# FTDI.net
KiCad netlist of a schematic drawn in Altium Designer
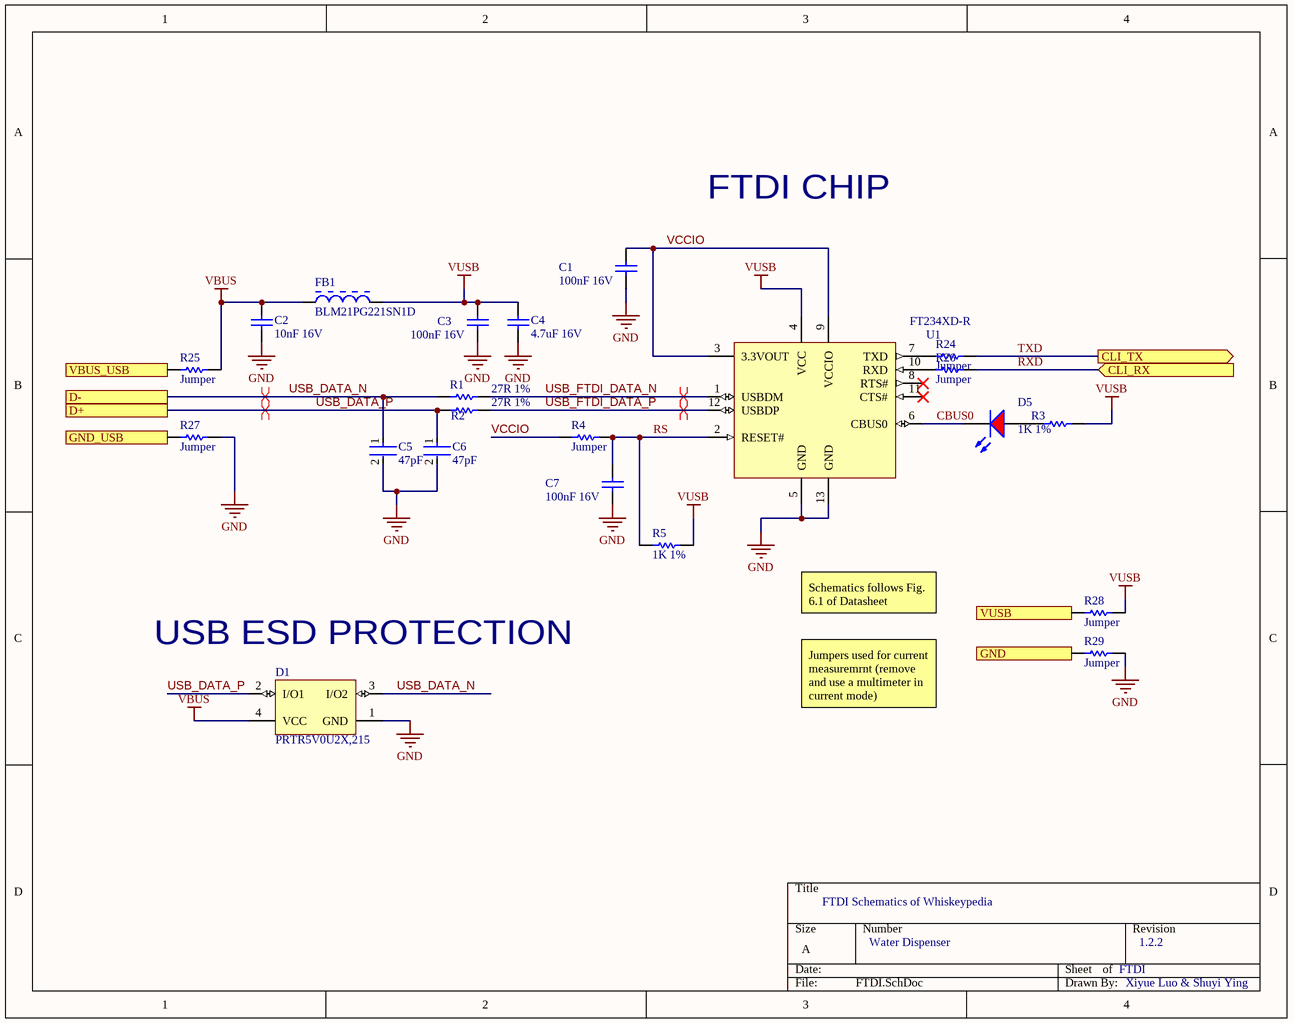
[diagram p0: FTDI.SchDoc]

(export (version "E")
  (design (tool "Eeschema 10.0.6"))
  (components
    (comp (ref "C1")
      (value "100nF 16V")
      (footprint "CAPC0603(1608)100_N")
      (description "CAP 100nF 16V ±10% 0603 (1608 Metric) Thickness 1mm SMD")
      (fields (field (name "TOLERANCE") "Â±10%"))
      (libsource (lib "Altium Content Vault") (part "CAP"))
    )
    (comp (ref "C2")
      (value "10nF 16V")
      (footprint "CAPC0603(1608)100_N")
      (description "CAP 10nF 16V ±10% 0603 (1608 Metric) Thickness 1mm SMD")
      (fields (field (name "TOLERANCE") "Â±10%"))
      (libsource (lib "Altium Content Vault") (part "CAP"))
    )
    (comp (ref "C3")
      (value "100nF 16V")
      (footprint "CAPC0603(1608)100_N")
      (description "CAP 100nF 16V ±10% 0603 (1608 Metric) Thickness 1mm SMD")
      (fields (field (name "TOLERANCE") "Â±10%"))
      (libsource (lib "Altium Content Vault") (part "CAP"))
    )
    (comp (ref "C4")
      (value "4.7uF 16V")
      (footprint "CAPC0805(2012)145_N")
      (description "CAP 4.7uF 16V -20% to +80% 0805 (2012 Metric) Thickness 1.45mm SMD")
      (fields (field (name "TOLERANCE") "-20% to +80%"))
      (libsource (lib "Altium Content Vault") (part "CAP"))
    )
    (comp (ref "C5")
      (value "47pF")
      (footprint "FP-C0603C-CF-MFG")
      (description "CAP CER 47PF 16V NP0 0603")
      (fields
        (field (name "OCTOPART") "https://octopart.com/c0603c470j4gac7867-kemet-2107619")
        (field (name "MANUFACTURER PART NUMBER") "C0603C470J4GAC7867")
      )
      (libsource (lib "Altium Content Vault") (part "b4654b650e69147ec39a6b967a45e02"))
    )
    (comp (ref "C6")
      (value "47pF")
      (footprint "FP-C0603C-CF-MFG")
      (description "CAP CER 47PF 16V NP0 0603")
      (fields
        (field (name "OCTOPART") "https://octopart.com/c0603c470j4gac7867-kemet-2107619")
        (field (name "MANUFACTURER PART NUMBER") "C0603C470J4GAC7867")
      )
      (libsource (lib "Altium Content Vault") (part "b4654b650e69147ec39a6b967a45e02"))
    )
    (comp (ref "C7")
      (value "100nF 16V")
      (footprint "CAPC0603(1608)100_N")
      (description "CAP 100nF 16V ±10% 0603 (1608 Metric) Thickness 1mm SMD")
      (fields (field (name "TOLERANCE") "Â±10%"))
      (libsource (lib "Altium Content Vault") (part "CAP"))
    )
    (comp (ref "D1")
      (value "PRTR5V0U2X,215")
      (footprint "NXP-SOT143B-4_V")
      (fields (field (name "MANUFACTURER") "NXP Semiconductors"))
      (libsource (lib "Altium Content Vault") (part "NXP-PRTR5V0U2X,215-4"))
    )
    (comp (ref "D5")
      (value "LTST-C170CKT")
      (footprint "LTST-C170CKT_V")
      (description "LED Uni-Color Red, 100 mW, 200 mA, -55 to 85 degC, 2-Pin SMD, RoHS, Tape and Reel")
      (fields (field (name "MANUFACTURER") "Lite-On"))
      (libsource (lib "Altium Content Vault") (part "LED-RED-AK-2"))
    )
    (comp (ref "FB1")
      (value "BLM21PG221SN1D")
      (footprint "MURA-BLM21-B20-CHIP-2_V2")
      (fields (field (name "MANUFACTURER") "Murata"))
      (libsource (lib "Altium Content Vault") (part "MURA-FB-2"))
    )
    (comp (ref "R1")
      (value "27R 1%")
      (footprint "RESC1005X40X25NL10T10")
      (fields (field (name "MANUFACTURER") "Multicomp") (field (name "PART NUMBER") "MC00625W0402127R"))
      (libsource (lib "Altium Content Vault") (part "RES"))
    )
    (comp (ref "R2")
      (value "27R 1%")
      (footprint "RESC1005X40X25NL10T10")
      (fields (field (name "MANUFACTURER") "Multicomp") (field (name "PART NUMBER") "MC00625W0402127R"))
      (libsource (lib "Altium Content Vault") (part "RES"))
    )
    (comp (ref "R3")
      (value "1K 1%")
      (footprint "RESC0603(1608)_N")
      (description "1K 0.1W 1% 0603 (1608 Metric)  SMD")
      (fields (field (name "TOLERANCE") "1 %") (field (name "POWER") "0.1 W"))
      (libsource (lib "Altium Content Vault") (part "RES"))
    )
    (comp (ref "R4")
      (value "Jumper")
      (footprint "RESC0805(2012)_N")
      (description "Jumper 0805 (2012 Metric)")
      (fields (field (name "TOLERANCE") "None"))
      (libsource (lib "Altium Content Vault") (part "RES"))
    )
    (comp (ref "R5")
      (value "1K 1%")
      (footprint "RESC0603(1608)_N")
      (description "1K 0.1W 1% 0603 (1608 Metric)  SMD")
      (fields (field (name "TOLERANCE") "1 %") (field (name "POWER") "0.1 W"))
      (libsource (lib "Altium Content Vault") (part "RES"))
    )
    (comp (ref "R24")
      (value "Jumper")
      (footprint "RESC0805(2012)_N")
      (description "Jumper 0805 (2012 Metric)")
      (fields (field (name "TOLERANCE") "None"))
      (libsource (lib "Altium Content Vault") (part "RES"))
    )
    (comp (ref "R25")
      (value "Jumper")
      (footprint "RESC0805(2012)_N")
      (description "Jumper 0805 (2012 Metric)")
      (fields (field (name "TOLERANCE") "None"))
      (libsource (lib "Altium Content Vault") (part "RES"))
    )
    (comp (ref "R26")
      (value "Jumper")
      (footprint "RESC0805(2012)_N")
      (description "Jumper 0805 (2012 Metric)")
      (fields (field (name "TOLERANCE") "None"))
      (libsource (lib "Altium Content Vault") (part "RES"))
    )
    (comp (ref "R27")
      (value "Jumper")
      (footprint "RESC0805(2012)_N")
      (description "Jumper 0805 (2012 Metric)")
      (fields (field (name "TOLERANCE") "None"))
      (libsource (lib "Altium Content Vault") (part "RES"))
    )
    (comp (ref "R28")
      (value "Jumper")
      (footprint "RESC0805(2012)_N")
      (description "Jumper 0805 (2012 Metric)")
      (fields (field (name "TOLERANCE") "None"))
      (libsource (lib "Altium Content Vault") (part "RES"))
    )
    (comp (ref "R29")
      (value "Jumper")
      (footprint "RESC0805(2012)_N")
      (description "Jumper 0805 (2012 Metric)")
      (fields (field (name "TOLERANCE") "None"))
      (libsource (lib "Altium Content Vault") (part "RES"))
    )
    (comp (ref "U1")
      (value "FT234XD-R")
      (footprint "DFN-12_V")
      (description "FT234XD USB to BASIC UART IC, -40 to +85 degC, 12-Pin DFN, Pb-Free, Tape and Reel")
      (fields (field (name "MANUFACTURER") "FTDI"))
      (libsource (lib "Altium Content Vault") (part "FTDI-FT234XD-DFN-12"))
    )
  )
  (nets
    (net (code "1") (name "/CBUS0") (class "Default")
      (node (ref "D5") (pin "2") (pinfunction "K_2") (pintype "passive"))
      (node (ref "U1") (pin "6") (pinfunction "CBUS0_6") (pintype "bidirectional"))
    )
    (net (code "2") (name "/GND_USB") (class "Default")
      (node (ref "R27") (pin "1") (pinfunction "1_1") (pintype "passive"))
    )
    (net (code "3") (name "/RS") (class "Default")
      (node (ref "C7") (pin "2") (pinfunction "2_2") (pintype "passive"))
      (node (ref "R4") (pin "2") (pinfunction "2_2") (pintype "passive"))
      (node (ref "R5") (pin "2") (pinfunction "2_2") (pintype "passive"))
      (node (ref "U1") (pin "2") (pinfunction "RESET#_2") (pintype "input"))
    )
    (net (code "4") (name "/RXD") (class "Default")
      (node (ref "R26") (pin "2") (pinfunction "2_2") (pintype "passive"))
    )
    (net (code "5") (name "/TXD") (class "Default")
      (node (ref "R24") (pin "2") (pinfunction "2_2") (pintype "passive"))
    )
    (net (code "6") (name "/USB_DATA_N") (class "Default")
      (node (ref "C5") (pin "1") (pinfunction "1_1") (pintype "passive"))
      (node (ref "D1") (pin "3") (pinfunction "I/O2_3") (pintype "bidirectional"))
      (node (ref "R1") (pin "1") (pinfunction "1_1") (pintype "passive"))
    )
    (net (code "7") (name "/USB_DATA_P") (class "Default")
      (node (ref "C6") (pin "1") (pinfunction "1_1") (pintype "passive"))
      (node (ref "D1") (pin "2") (pinfunction "I/O1_2") (pintype "bidirectional"))
      (node (ref "R2") (pin "1") (pinfunction "1_1") (pintype "passive"))
    )
    (net (code "8") (name "/USB_FTDI_DATA_N") (class "Default")
      (node (ref "R1") (pin "2") (pinfunction "2_2") (pintype "passive"))
      (node (ref "U1") (pin "1") (pinfunction "USBDM_1") (pintype "bidirectional"))
    )
    (net (code "9") (name "/USB_FTDI_DATA_P") (class "Default")
      (node (ref "R2") (pin "2") (pinfunction "2_2") (pintype "passive"))
      (node (ref "U1") (pin "12") (pinfunction "USBDP_12") (pintype "bidirectional"))
    )
    (net (code "10") (name "/VBUS_USB") (class "Default")
      (node (ref "R25") (pin "1") (pinfunction "1_1") (pintype "passive"))
    )
    (net (code "11") (name "/VCCIO") (class "Default")
      (node (ref "C1") (pin "2") (pinfunction "2_2") (pintype "passive"))
      (node (ref "R4") (pin "1") (pinfunction "1_1") (pintype "passive"))
      (node (ref "U1") (pin "3") (pinfunction "3.3VOUT_3") (pintype "power_in"))
      (node (ref "U1") (pin "9") (pinfunction "VCCIO_9") (pintype "power_in"))
    )
    (net (code "12") (name "GND") (class "Default")
      (node (ref "C1") (pin "1") (pinfunction "1_1") (pintype "passive"))
      (node (ref "C2") (pin "1") (pinfunction "1_1") (pintype "passive"))
      (node (ref "C3") (pin "1") (pinfunction "1_1") (pintype "passive"))
      (node (ref "C4") (pin "1") (pinfunction "1_1") (pintype "passive"))
      (node (ref "C5") (pin "2") (pinfunction "2_2") (pintype "passive"))
      (node (ref "C6") (pin "2") (pinfunction "2_2") (pintype "passive"))
      (node (ref "C7") (pin "1") (pinfunction "1_1") (pintype "passive"))
      (node (ref "D1") (pin "1") (pinfunction "GND_1") (pintype "power_in"))
      (node (ref "R27") (pin "2") (pinfunction "2_2") (pintype "passive"))
      (node (ref "R29") (pin "1") (pinfunction "1_1") (pintype "passive"))
      (node (ref "R29") (pin "2") (pinfunction "2_2") (pintype "passive"))
      (node (ref "U1") (pin "13") (pinfunction "GND_13") (pintype "power_in"))
      (node (ref "U1") (pin "5") (pinfunction "GND_5") (pintype "power_in"))
    )
    (net (code "13") (name "Net-(D5-A)") (class "Default")
      (node (ref "D5") (pin "1") (pinfunction "A_1") (pintype "passive"))
      (node (ref "R3") (pin "1") (pinfunction "1_1") (pintype "passive"))
    )
    (net (code "14") (name "Net-(U1-RXD)") (class "Default")
      (node (ref "R26") (pin "1") (pinfunction "1_1") (pintype "passive"))
      (node (ref "U1") (pin "10") (pinfunction "RXD_10") (pintype "input"))
    )
    (net (code "15") (name "Net-(U1-TXD)") (class "Default")
      (node (ref "R24") (pin "1") (pinfunction "1_1") (pintype "passive"))
      (node (ref "U1") (pin "7") (pinfunction "TXD_7") (pintype "output"))
    )
    (net (code "16") (name "VBUS") (class "Default")
      (node (ref "C2") (pin "2") (pinfunction "2_2") (pintype "passive"))
      (node (ref "D1") (pin "4") (pinfunction "VCC_4") (pintype "power_in"))
      (node (ref "FB1") (pin "1") (pinfunction "1_1") (pintype "passive"))
      (node (ref "R25") (pin "2") (pinfunction "2_2") (pintype "passive"))
    )
    (net (code "17") (name "VUSB") (class "Default")
      (node (ref "C3") (pin "2") (pinfunction "2_2") (pintype "passive"))
      (node (ref "C4") (pin "2") (pinfunction "2_2") (pintype "passive"))
      (node (ref "FB1") (pin "2") (pinfunction "2_2") (pintype "passive"))
      (node (ref "R28") (pin "1") (pinfunction "1_1") (pintype "passive"))
      (node (ref "R28") (pin "2") (pinfunction "2_2") (pintype "passive"))
      (node (ref "R3") (pin "2") (pinfunction "2_2") (pintype "passive"))
      (node (ref "R5") (pin "1") (pinfunction "1_1") (pintype "passive"))
      (node (ref "U1") (pin "4") (pinfunction "VCC_4") (pintype "power_in"))
    )
    (net (code "18") (name "unconnected-(U1-CTS#-Pad11)") (class "Default")
      (node (ref "U1") (pin "11") (pinfunction "CTS#_11") (pintype "input+no_connect"))
    )
    (net (code "19") (name "unconnected-(U1-RTS#-Pad8)") (class "Default")
      (node (ref "U1") (pin "8") (pinfunction "RTS#_8") (pintype "output+no_connect"))
    )
  )
)
